# EDP_Retrofit.net
KiCad netlist of a schematic drawn in Altium Designer
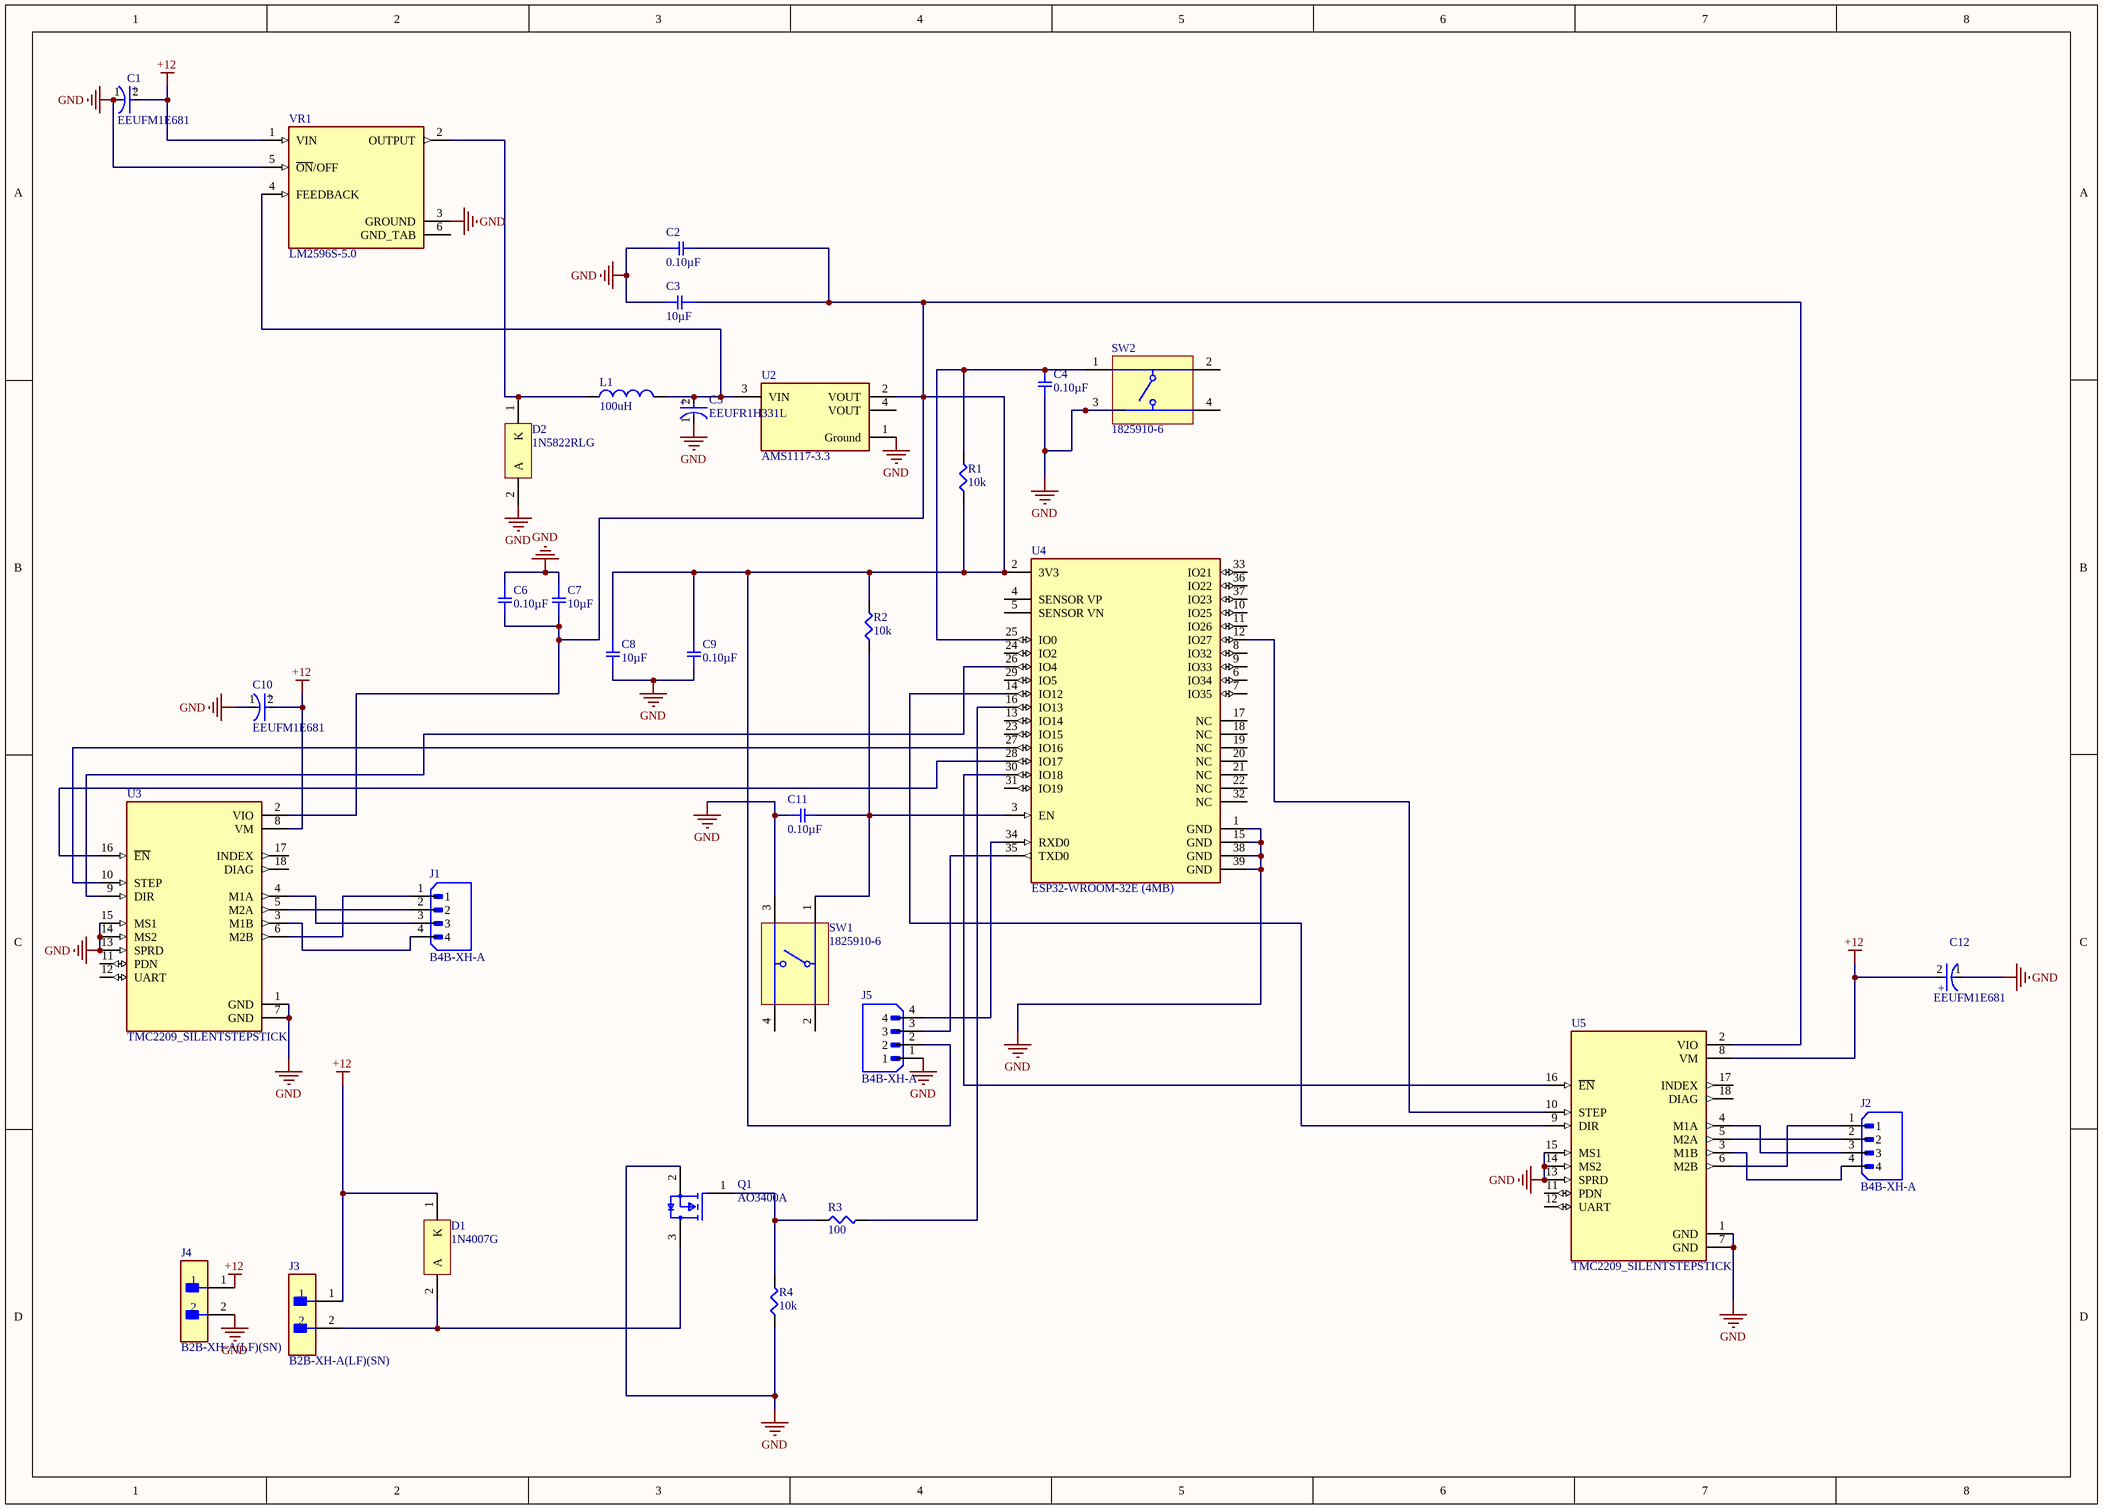
[diagram p0: EDP_Retrofit.SchDoc]

(export (version "E")
  (design (tool "Eeschema 10.0.6"))
  (components
    (comp (ref "C1")
      (value "EEUFM1E681")
      (footprint "FP-RAD-TH-D_10_0_5-L_20_2-MFG")
      (description "Aluminum Electrolytic Capacitors (Radial Lead Type) 680uF ±20% 25V")
      (fields (field (name "VOLTAGE") "25V") (field (name "TOLERANCE") "20%"))
      (libsource (lib "Altium Content Vault") (part "203bc49f2ac43e59fd269a8c329ed05"))
    )
    (comp (ref "C2")
      (value "0.10µF")
      (footprint "SMD-0805C")
      (description "CAP CER 0.1UF 25V X7R 0805")
      (fields
        (field (name "DIGI-KEY PART NUMBER") "490-1673-1-ND")
        (field (name "PART NUMBER") "GRM21BR71E104KA01L")
      )
      (libsource (lib "capacitor_murata_0805") (part "GRM21BR71E104KA01L"))
    )
    (comp (ref "C3")
      (value "10µF")
      (footprint "SMD-0805C")
      (description "CAP CER 10UF 10V X7R 0805")
      (fields
        (field (name "DIGI-KEY PART NUMBER") "490-12646-1-ND")
        (field (name "PART NUMBER") "GCJ21BR71A106KE01L")
      )
      (libsource (lib "capacitor_murata_0805") (part "GCJ21BR71A106KE01L"))
    )
    (comp (ref "C4")
      (value "0.10µF")
      (footprint "SMD-0805C")
      (description "CAP CER 0.1UF 25V X7R 0805")
      (fields
        (field (name "DIGI-KEY PART NUMBER") "490-1673-1-ND")
        (field (name "PART NUMBER") "GRM21BR71E104KA01L")
      )
      (libsource (lib "capacitor_murata_0805") (part "GRM21BR71E104KA01L"))
    )
    (comp (ref "C5")
      (value "EEUFR1H331L")
      (footprint "FP-RAD-TH-D_10_0_5-L_25_2-MFG")
      (description "Aluminum Electrolytic Capacitors (Radial Lead Type) 330uF ±20% 50V")
      (libsource (lib "Altium Content Vault") (part "a00bbbee19879c290e62620ae7e47b1"))
    )
    (comp (ref "C6")
      (value "0.10µF")
      (footprint "SMD-0805C")
      (description "CAP CER 0.1UF 25V X7R 0805")
      (fields
        (field (name "DIGI-KEY PART NUMBER") "490-1673-1-ND")
        (field (name "PART NUMBER") "GRM21BR71E104KA01L")
      )
      (libsource (lib "capacitor_murata_0805") (part "GRM21BR71E104KA01L"))
    )
    (comp (ref "C7")
      (value "10µF")
      (footprint "SMD-0805C")
      (description "CAP CER 10UF 10V X7R 0805")
      (fields
        (field (name "DIGI-KEY PART NUMBER") "490-12646-1-ND")
        (field (name "PART NUMBER") "GCJ21BR71A106KE01L")
      )
      (libsource (lib "capacitor_murata_0805") (part "GCJ21BR71A106KE01L"))
    )
    (comp (ref "C8")
      (value "10µF")
      (footprint "SMD-0805C")
      (description "CAP CER 10UF 10V X7R 0805")
      (fields
        (field (name "DIGI-KEY PART NUMBER") "490-12646-1-ND")
        (field (name "PART NUMBER") "GCJ21BR71A106KE01L")
      )
      (libsource (lib "capacitor_murata_0805") (part "GCJ21BR71A106KE01L"))
    )
    (comp (ref "C9")
      (value "0.10µF")
      (footprint "SMD-0805C")
      (description "CAP CER 0.1UF 25V X7R 0805")
      (fields
        (field (name "DIGI-KEY PART NUMBER") "490-1673-1-ND")
        (field (name "PART NUMBER") "GRM21BR71E104KA01L")
      )
      (libsource (lib "capacitor_murata_0805") (part "GRM21BR71E104KA01L"))
    )
    (comp (ref "C10")
      (value "EEUFM1E681")
      (footprint "FP-RAD-TH-D_10_0_5-L_20_2-MFG")
      (description "Aluminum Electrolytic Capacitors (Radial Lead Type) 680uF ±20% 25V")
      (fields (field (name "VOLTAGE") "25V") (field (name "TOLERANCE") "20%"))
      (libsource (lib "Altium Content Vault") (part "203bc49f2ac43e59fd269a8c329ed05"))
    )
    (comp (ref "C11")
      (value "0.10µF")
      (footprint "SMD-0805C")
      (description "CAP CER 0.1UF 25V X7R 0805")
      (fields
        (field (name "DIGI-KEY PART NUMBER") "490-1673-1-ND")
        (field (name "PART NUMBER") "GRM21BR71E104KA01L")
      )
      (libsource (lib "capacitor_murata_0805") (part "GRM21BR71E104KA01L"))
    )
    (comp (ref "C12")
      (value "EEUFM1E681")
      (footprint "FP-RAD-TH-D_10_0_5-L_20_2-MFG")
      (description "Aluminum Electrolytic Capacitors (Radial Lead Type) 680uF ±20% 25V")
      (fields (field (name "VOLTAGE") "25V") (field (name "TOLERANCE") "20%"))
      (libsource (lib "Altium Content Vault") (part "203bc49f2ac43e59fd269a8c329ed05"))
    )
    (comp (ref "D1")
      (value "1N4007G")
      (footprint "ONSC-AXIAL_LEAD-2-59-10_P")
      (description "Standard Recovery Rectifier, 2-Pin Axial_Lead, Pb-Free, Bulk Bag")
      (fields (field (name "MANUFACTURER") "On Semiconductor"))
      (libsource (lib "Altium Content Vault") (part "ONSC-D-K1A2-2_A"))
    )
    (comp (ref "D2")
      (value "1N5822RLG")
      (footprint "ONSC-AXIAL_LEAD-2-267-05_V")
      (description "Rectifier, 2-Pin Axial_Lead, Pb-Free, Tape and Reel")
      (fields (field (name "MANUFACTURER") "On Semiconductor"))
      (libsource (lib "Altium Content Vault") (part "ONSC-D-K1A2-2_A"))
    )
    (comp (ref "J1")
      (value "B4B-XH-A")
      (footprint "JST_B4B-XH-A")
      (description "Connector Header Through Hole 4 position 0.098 (2.50mm)")
      (fields (field (name "MF") "JST Sales"))
      (libsource (lib "B4B-XH-A") (part "B4B-XH-A"))
    )
    (comp (ref "J2")
      (value "B4B-XH-A")
      (footprint "JST_B4B-XH-A")
      (description "Connector Header Through Hole 4 position 0.098 (2.50mm)")
      (fields (field (name "MF") "JST Sales"))
      (libsource (lib "B4B-XH-A") (part "B4B-XH-A"))
    )
    (comp (ref "J3")
      (value "B2B-XH-A(LF)(SN)")
      (footprint "FP-B2B-XH-A_LF_SN-MFG")
      (description "CONN HEADER VERT 2POS 2.5MM")
      (libsource (lib "Altium Content Vault") (part "3bc925449376181038e59eaffc5286c"))
    )
    (comp (ref "J4")
      (value "B2B-XH-A(LF)(SN)")
      (footprint "FP-B2B-XH-A_LF_SN-MFG")
      (description "CONN HEADER VERT 2POS 2.5MM")
      (libsource (lib "Altium Content Vault") (part "3bc925449376181038e59eaffc5286c"))
    )
    (comp (ref "J5")
      (value "B4B-XH-A")
      (footprint "JST_B4B-XH-A")
      (description "Connector Header Through Hole 4 position 0.098 (2.50mm)")
      (fields (field (name "MF") "JST Sales"))
      (libsource (lib "") (part "B4B-XH-A_1"))
    )
    (comp (ref "L1")
      (value "100uH")
      (footprint "MY_0805")
      (description "Inductor")
      (fields (field (name "ASID PART NUMBER") "Inductor-AS"))
      (libsource (lib "Custom_Components") (part "Inductor"))
    )
    (comp (ref "Q1")
      (value "AO3400A")
      (footprint "FP-SOT23-MFG")
      (description "MOSFET N-CH 30V 5.7A SOT23")
      (libsource (lib "Altium Content Vault") (part "0a9ea7c96deaaede766a5b531c28de0"))
    )
    (comp (ref "R1")
      (value "10k")
      (footprint "SMD-0805-RES")
      (description "RES SMD 10K OHM 1% 1/8W 0805")
      (fields
        (field (name "PART NUMBER") "ERJ-6ENF1002V")
        (field (name "DIGI-KEY PART NUMBER") "P10.0KCCT-ND")
      )
      (libsource (lib "Panasonic_ERJ_0805") (part "ERJ-6ENF1002V"))
    )
    (comp (ref "R2")
      (value "10k")
      (footprint "SMD-0805-RES")
      (description "RES SMD 10K OHM 1% 1/8W 0805")
      (fields
        (field (name "PART NUMBER") "ERJ-6ENF1002V")
        (field (name "DIGI-KEY PART NUMBER") "P10.0KCCT-ND")
      )
      (libsource (lib "Panasonic_ERJ_0805") (part "ERJ-6ENF1002V"))
    )
    (comp (ref "R3")
      (value "100")
      (footprint "SMD-0805-RES")
      (description "RES SMD 100 OHM 1% 1/8W 0805")
      (fields (field (name "PART NUMBER") "ERJ-6ENF1000V") (field (name "DIGI-KEY PART NUMBER") "P100CCT-ND"))
      (libsource (lib "Panasonic_ERJ_0805") (part "ERJ-6ENF1000V"))
    )
    (comp (ref "R4")
      (value "10k")
      (footprint "SMD-0805-RES")
      (description "RES SMD 10K OHM 1% 1/8W 0805")
      (fields
        (field (name "PART NUMBER") "ERJ-6ENF1002V")
        (field (name "DIGI-KEY PART NUMBER") "P10.0KCCT-ND")
      )
      (libsource (lib "Panasonic_ERJ_0805") (part "ERJ-6ENF1002V"))
    )
    (comp (ref "SW1")
      (value "1825910-6")
      (footprint "TECO-1825910-6_V")
      (description "Tact Switch, SPST-NO, 0.05 A, -35 to 85 degC, 4-Pin THD, RoHS, Bulk")
      (fields (field (name "MANUFACTURER") "TE Connectivity"))
      (libsource (lib "") (part "SW-SPST-4_A_1"))
    )
    (comp (ref "SW2")
      (value "1825910-6")
      (footprint "TECO-1825910-6_V")
      (description "Tact Switch, SPST-NO, 0.05 A, -35 to 85 degC, 4-Pin THD, RoHS, Bulk")
      (fields (field (name "MANUFACTURER") "TE Connectivity"))
      (libsource (lib "Altium Content Vault") (part "SW-SPST-4_A"))
    )
    (comp (ref "U2")
      (value "AMS1117-3.3")
      (footprint "FP-AMS1117-IPC_C")
      (description "LDO Voltage Regulators 1A, 3.3V")
      (fields
        (field (name "OCTOPART") "https://octopart.com/ams1117-3.3-advanced+monolithic+systems-25899300")
        (field (name "MANUFACTURER") "Advanced Monolithic Systems")
      )
      (libsource (lib "Altium Content Vault") (part "8bdbb5f8e77002000e30dd2845d0354"))
    )
    (comp (ref "U3")
      (value "TMC2209_SILENTSTEPSTICK")
      (footprint "MODULE_TMC2209_SILENTSTEPSTICK")
      (description "TMC2209 Motor Controller/Driver Power Management Evaluation Board")
      (fields
        (field (name "MF") "Trinamic Motion Control GmbH")
        (field (name "MP") "TMC2209 SILENTSTEPSTICK")
      )
      (libsource (lib "TMC2209_SILENTSTEPSTICK") (part "TMC2209_SILENTSTEPSTICK"))
    )
    (comp (ref "U4")
      (value "ESP32-WROOM-32E (4MB)")
      (footprint "FP-ESP32-WROOM-32E_4MB-MFG")
      (description "RX TXRX MOD WIFI TRACE ANT SMD")
      (libsource (lib "Altium Content Vault") (part "7f842c3463a9561e2f6f9fdcd687e0f"))
    )
    (comp (ref "U5")
      (value "TMC2209_SILENTSTEPSTICK")
      (footprint "MODULE_TMC2209_SILENTSTEPSTICK")
      (description "TMC2209 Motor Controller/Driver Power Management Evaluation Board")
      (fields
        (field (name "MF") "Trinamic Motion Control GmbH")
        (field (name "MP") "TMC2209 SILENTSTEPSTICK")
      )
      (libsource (lib "TMC2209_SILENTSTEPSTICK") (part "TMC2209_SILENTSTEPSTICK"))
    )
    (comp (ref "VR1")
      (value "LM2596S-5.0")
      (footprint "TO170P1524X483-6N")
      (description "SIMPLE SWITCHERÂ® 4.5V to 40V, 3A Low Component Count Step-Down Regulator")
      (fields (field (name "MF") "Texas Instruments") (field (name "MP") "LM2596S-5.0/NOPB"))
      (libsource (lib "LM2596S-5.0") (part "LM2596S-5.0"))
    )
  )
  (nets
    (net (code "1") (name "+12") (class "Default")
      (node (ref "C1") (pin "2") (pinfunction "A_2") (pintype "passive"))
      (node (ref "C10") (pin "2") (pinfunction "A_2") (pintype "passive"))
      (node (ref "C12") (pin "2") (pinfunction "A_2") (pintype "passive"))
      (node (ref "D1") (pin "1") (pinfunction "K_1") (pintype "passive"))
      (node (ref "J3") (pin "1") (pinfunction "1_1") (pintype "passive"))
      (node (ref "J4") (pin "1") (pinfunction "1_1") (pintype "passive"))
      (node (ref "U3") (pin "8") (pinfunction "VM_8") (pintype "power_in"))
      (node (ref "U5") (pin "8") (pinfunction "VM_8") (pintype "power_in"))
      (node (ref "VR1") (pin "1") (pinfunction "VIN_1") (pintype "input"))
    )
    (net (code "2") (name "GND") (class "Default")
      (node (ref "C1") (pin "1") (pinfunction "C_1") (pintype "passive"))
      (node (ref "C10") (pin "1") (pinfunction "C_1") (pintype "passive"))
      (node (ref "C11") (pin "1") (pinfunction "1_1") (pintype "passive"))
      (node (ref "C12") (pin "1") (pinfunction "C_1") (pintype "passive"))
      (node (ref "C2") (pin "1") (pinfunction "1_1") (pintype "passive"))
      (node (ref "C3") (pin "2") (pinfunction "2_2") (pintype "passive"))
      (node (ref "C4") (pin "2") (pinfunction "2_2") (pintype "passive"))
      (node (ref "C5") (pin "1") (pinfunction "C_1") (pintype "passive"))
      (node (ref "C6") (pin "1") (pinfunction "1_1") (pintype "passive"))
      (node (ref "C7") (pin "1") (pinfunction "1_1") (pintype "passive"))
      (node (ref "C8") (pin "2") (pinfunction "2_2") (pintype "passive"))
      (node (ref "C9") (pin "2") (pinfunction "2_2") (pintype "passive"))
      (node (ref "D2") (pin "2") (pinfunction "A_2") (pintype "passive"))
      (node (ref "J4") (pin "2") (pinfunction "2_2") (pintype "passive"))
      (node (ref "J5") (pin "1") (pinfunction "1_1") (pintype "passive"))
      (node (ref "Q1") (pin "2") (pinfunction "S_2") (pintype "passive"))
      (node (ref "R4") (pin "1") (pinfunction "1_1") (pintype "passive"))
      (node (ref "SW1") (pin "3") (pinfunction "3_3") (pintype "passive"))
      (node (ref "SW2") (pin "3") (pinfunction "3_3") (pintype "passive"))
      (node (ref "U2") (pin "1") (pinfunction "Ground_1") (pintype "power_in"))
      (node (ref "U3") (pin "1") (pinfunction "GND_1") (pintype "power_in"))
      (node (ref "U3") (pin "13") (pinfunction "SPRD_13") (pintype "input"))
      (node (ref "U3") (pin "14") (pinfunction "MS2_14") (pintype "input"))
      (node (ref "U3") (pin "15") (pinfunction "MS1_15") (pintype "input"))
      (node (ref "U3") (pin "7") (pinfunction "GND_7") (pintype "power_in"))
      (node (ref "U4") (pin "1") (pinfunction "GND_1") (pintype "power_in"))
      (node (ref "U4") (pin "15") (pinfunction "GND_15") (pintype "power_in"))
      (node (ref "U4") (pin "38") (pinfunction "GND_38") (pintype "power_in"))
      (node (ref "U4") (pin "39") (pinfunction "GND_39") (pintype "power_in"))
      (node (ref "U5") (pin "1") (pinfunction "GND_1") (pintype "power_in"))
      (node (ref "U5") (pin "13") (pinfunction "SPRD_13") (pintype "input"))
      (node (ref "U5") (pin "14") (pinfunction "MS2_14") (pintype "input"))
      (node (ref "U5") (pin "15") (pinfunction "MS1_15") (pintype "input"))
      (node (ref "U5") (pin "7") (pinfunction "GND_7") (pintype "power_in"))
      (node (ref "VR1") (pin "3") (pinfunction "GROUND_3") (pintype "power_in"))
      (node (ref "VR1") (pin "5") (pinfunction "~{ON}/OFF_5") (pintype "input"))
    )
    (net (code "3") (name "Net-(C5-A)") (class "Default")
      (node (ref "C5") (pin "2") (pinfunction "A_2") (pintype "passive"))
      (node (ref "L1") (pin "2") (pinfunction "2_2") (pintype "passive"))
      (node (ref "U2") (pin "3") (pinfunction "VIN_3") (pintype "power_in"))
      (node (ref "VR1") (pin "4") (pinfunction "FEEDBACK_4") (pintype "input"))
    )
    (net (code "4") (name "Net-(D1-A)") (class "Default")
      (node (ref "D1") (pin "2") (pinfunction "A_2") (pintype "passive"))
      (node (ref "J3") (pin "2") (pinfunction "2_2") (pintype "passive"))
      (node (ref "Q1") (pin "3") (pinfunction "D_3") (pintype "passive"))
    )
    (net (code "5") (name "Net-(D2-K)") (class "Default")
      (node (ref "D2") (pin "1") (pinfunction "K_1") (pintype "passive"))
      (node (ref "L1") (pin "1") (pinfunction "1_1") (pintype "passive"))
      (node (ref "VR1") (pin "2") (pinfunction "OUTPUT_2") (pintype "output"))
    )
    (net (code "6") (name "Net-(Q1-G)") (class "Default")
      (node (ref "Q1") (pin "1") (pinfunction "G_1") (pintype "passive"))
      (node (ref "R3") (pin "1") (pinfunction "1_1") (pintype "passive"))
      (node (ref "R4") (pin "2") (pinfunction "2_2") (pintype "passive"))
    )
    (net (code "7") (name "Net-(U3-DIR)") (class "Default")
      (node (ref "U3") (pin "9") (pinfunction "DIR_9") (pintype "input"))
      (node (ref "U4") (pin "26") (pinfunction "IO4_26") (pintype "bidirectional"))
    )
    (net (code "8") (name "Net-(U3-M1A)") (class "Default")
      (node (ref "J1") (pin "3") (pinfunction "3_3") (pintype "passive"))
      (node (ref "U3") (pin "4") (pinfunction "M1A_4") (pintype "output"))
    )
    (net (code "9") (name "Net-(U3-M1B)") (class "Default")
      (node (ref "J1") (pin "4") (pinfunction "4_4") (pintype "passive"))
      (node (ref "U3") (pin "3") (pinfunction "M1B_3") (pintype "output"))
    )
    (net (code "10") (name "Net-(U3-M2A)") (class "Default")
      (node (ref "J1") (pin "2") (pinfunction "2_2") (pintype "passive"))
      (node (ref "U3") (pin "5") (pinfunction "M2A_5") (pintype "output"))
    )
    (net (code "11") (name "Net-(U3-M2B)") (class "Default")
      (node (ref "J1") (pin "1") (pinfunction "1_1") (pintype "passive"))
      (node (ref "U3") (pin "6") (pinfunction "M2B_6") (pintype "output"))
    )
    (net (code "12") (name "Net-(U3-STEP)") (class "Default")
      (node (ref "U3") (pin "10") (pinfunction "STEP_10") (pintype "input"))
      (node (ref "U4") (pin "27") (pinfunction "IO16_27") (pintype "bidirectional"))
    )
    (net (code "13") (name "Net-(U3-VIO)") (class "Default")
      (node (ref "C2") (pin "2") (pinfunction "2_2") (pintype "passive"))
      (node (ref "C3") (pin "1") (pinfunction "1_1") (pintype "passive"))
      (node (ref "C6") (pin "2") (pinfunction "2_2") (pintype "passive"))
      (node (ref "C7") (pin "2") (pinfunction "2_2") (pintype "passive"))
      (node (ref "C8") (pin "1") (pinfunction "1_1") (pintype "passive"))
      (node (ref "C9") (pin "1") (pinfunction "1_1") (pintype "passive"))
      (node (ref "J5") (pin "2") (pinfunction "2_2") (pintype "passive"))
      (node (ref "R1") (pin "1") (pinfunction "1_1") (pintype "passive"))
      (node (ref "R2") (pin "2") (pinfunction "2_2") (pintype "passive"))
      (node (ref "U2") (pin "2") (pinfunction "VOUT_2") (pintype "passive"))
      (node (ref "U3") (pin "2") (pinfunction "VIO_2") (pintype "power_in"))
      (node (ref "U4") (pin "2") (pinfunction "3V3_2") (pintype "power_in"))
      (node (ref "U5") (pin "2") (pinfunction "VIO_2") (pintype "power_in"))
    )
    (net (code "14") (name "Net-(U3-~{EN})") (class "Default")
      (node (ref "U3") (pin "16") (pinfunction "~{EN}_16") (pintype "input"))
      (node (ref "U4") (pin "28") (pinfunction "IO17_28") (pintype "bidirectional"))
    )
    (net (code "15") (name "Net-(U4-EN)") (class "Default")
      (node (ref "C11") (pin "2") (pinfunction "2_2") (pintype "passive"))
      (node (ref "R2") (pin "1") (pinfunction "1_1") (pintype "passive"))
      (node (ref "SW1") (pin "1") (pinfunction "1_1") (pintype "passive"))
      (node (ref "U4") (pin "3") (pinfunction "EN_3") (pintype "input"))
    )
    (net (code "16") (name "Net-(U4-IO0)") (class "Default")
      (node (ref "C4") (pin "1") (pinfunction "1_1") (pintype "passive"))
      (node (ref "R1") (pin "2") (pinfunction "2_2") (pintype "passive"))
      (node (ref "SW2") (pin "1") (pinfunction "1_1") (pintype "passive"))
      (node (ref "U4") (pin "25") (pinfunction "IO0_25") (pintype "bidirectional"))
    )
    (net (code "17") (name "Net-(U4-IO12)") (class "Default")
      (node (ref "U4") (pin "14") (pinfunction "IO12_14") (pintype "bidirectional"))
      (node (ref "U5") (pin "9") (pinfunction "DIR_9") (pintype "input"))
    )
    (net (code "18") (name "Net-(U4-IO13)") (class "Default")
      (node (ref "R3") (pin "2") (pinfunction "2_2") (pintype "passive"))
      (node (ref "U4") (pin "16") (pinfunction "IO13_16") (pintype "bidirectional"))
    )
    (net (code "19") (name "Net-(U4-IO18)") (class "Default")
      (node (ref "U4") (pin "30") (pinfunction "IO18_30") (pintype "bidirectional"))
      (node (ref "U5") (pin "16") (pinfunction "~{EN}_16") (pintype "input"))
    )
    (net (code "20") (name "Net-(U4-IO27)") (class "Default")
      (node (ref "U4") (pin "12") (pinfunction "IO27_12") (pintype "bidirectional"))
      (node (ref "U5") (pin "10") (pinfunction "STEP_10") (pintype "input"))
    )
    (net (code "21") (name "Net-(U4-RXD0)") (class "Default")
      (node (ref "J5") (pin "4") (pinfunction "4_4") (pintype "passive"))
      (node (ref "U4") (pin "34") (pinfunction "RXD0_34") (pintype "input"))
    )
    (net (code "22") (name "Net-(U4-TXD0)") (class "Default")
      (node (ref "J5") (pin "3") (pinfunction "3_3") (pintype "passive"))
      (node (ref "U4") (pin "35") (pinfunction "TXD0_35") (pintype "output"))
    )
    (net (code "23") (name "Net-(U5-M1A)") (class "Default")
      (node (ref "J2") (pin "3") (pinfunction "3_3") (pintype "passive"))
      (node (ref "U5") (pin "4") (pinfunction "M1A_4") (pintype "output"))
    )
    (net (code "24") (name "Net-(U5-M1B)") (class "Default")
      (node (ref "J2") (pin "4") (pinfunction "4_4") (pintype "passive"))
      (node (ref "U5") (pin "3") (pinfunction "M1B_3") (pintype "output"))
    )
    (net (code "25") (name "Net-(U5-M2A)") (class "Default")
      (node (ref "J2") (pin "2") (pinfunction "2_2") (pintype "passive"))
      (node (ref "U5") (pin "5") (pinfunction "M2A_5") (pintype "output"))
    )
    (net (code "26") (name "Net-(U5-M2B)") (class "Default")
      (node (ref "J2") (pin "1") (pinfunction "1_1") (pintype "passive"))
      (node (ref "U5") (pin "6") (pinfunction "M2B_6") (pintype "output"))
    )
    (net (code "27") (name "unconnected-(SW1-Pad2)") (class "Default")
      (node (ref "SW1") (pin "2") (pinfunction "2_2") (pintype "passive"))
    )
    (net (code "28") (name "unconnected-(SW1-Pad4)") (class "Default")
      (node (ref "SW1") (pin "4") (pinfunction "4_4") (pintype "passive"))
    )
    (net (code "29") (name "unconnected-(SW2-Pad2)") (class "Default")
      (node (ref "SW2") (pin "2") (pinfunction "2_2") (pintype "passive"))
    )
    (net (code "30") (name "unconnected-(SW2-Pad4)") (class "Default")
      (node (ref "SW2") (pin "4") (pinfunction "4_4") (pintype "passive"))
    )
    (net (code "31") (name "unconnected-(U2-VOUT-Pad4)") (class "Default")
      (node (ref "U2") (pin "4") (pinfunction "VOUT_4") (pintype "passive"))
    )
    (net (code "32") (name "unconnected-(U3-DIAG-Pad18)") (class "Default")
      (node (ref "U3") (pin "18") (pinfunction "DIAG_18") (pintype "output"))
    )
    (net (code "33") (name "unconnected-(U3-INDEX-Pad17)") (class "Default")
      (node (ref "U3") (pin "17") (pinfunction "INDEX_17") (pintype "output"))
    )
    (net (code "34") (name "unconnected-(U3-PDN-Pad11)") (class "Default")
      (node (ref "U3") (pin "11") (pinfunction "PDN_11") (pintype "bidirectional"))
    )
    (net (code "35") (name "unconnected-(U3-UART-Pad12)") (class "Default")
      (node (ref "U3") (pin "12") (pinfunction "UART_12") (pintype "bidirectional"))
    )
    (net (code "36") (name "unconnected-(U4-IO2-Pad24)") (class "Default")
      (node (ref "U4") (pin "24") (pinfunction "IO2_24") (pintype "bidirectional"))
    )
    (net (code "37") (name "unconnected-(U4-IO5-Pad29)") (class "Default")
      (node (ref "U4") (pin "29") (pinfunction "IO5_29") (pintype "bidirectional"))
    )
    (net (code "38") (name "unconnected-(U4-IO14-Pad13)") (class "Default")
      (node (ref "U4") (pin "13") (pinfunction "IO14_13") (pintype "bidirectional"))
    )
    (net (code "39") (name "unconnected-(U4-IO15-Pad23)") (class "Default")
      (node (ref "U4") (pin "23") (pinfunction "IO15_23") (pintype "bidirectional"))
    )
    (net (code "40") (name "unconnected-(U4-IO19-Pad31)") (class "Default")
      (node (ref "U4") (pin "31") (pinfunction "IO19_31") (pintype "bidirectional"))
    )
    (net (code "41") (name "unconnected-(U4-IO21-Pad33)") (class "Default")
      (node (ref "U4") (pin "33") (pinfunction "IO21_33") (pintype "bidirectional"))
    )
    (net (code "42") (name "unconnected-(U4-IO22-Pad36)") (class "Default")
      (node (ref "U4") (pin "36") (pinfunction "IO22_36") (pintype "bidirectional"))
    )
    (net (code "43") (name "unconnected-(U4-IO23-Pad37)") (class "Default")
      (node (ref "U4") (pin "37") (pinfunction "IO23_37") (pintype "bidirectional"))
    )
    (net (code "44") (name "unconnected-(U4-IO25-Pad10)") (class "Default")
      (node (ref "U4") (pin "10") (pinfunction "IO25_10") (pintype "bidirectional"))
    )
    (net (code "45") (name "unconnected-(U4-IO26-Pad11)") (class "Default")
      (node (ref "U4") (pin "11") (pinfunction "IO26_11") (pintype "bidirectional"))
    )
    (net (code "46") (name "unconnected-(U4-IO32-Pad8)") (class "Default")
      (node (ref "U4") (pin "8") (pinfunction "IO32_8") (pintype "bidirectional"))
    )
    (net (code "47") (name "unconnected-(U4-IO33-Pad9)") (class "Default")
      (node (ref "U4") (pin "9") (pinfunction "IO33_9") (pintype "bidirectional"))
    )
    (net (code "48") (name "unconnected-(U4-IO34-Pad6)") (class "Default")
      (node (ref "U4") (pin "6") (pinfunction "IO34_6") (pintype "bidirectional"))
    )
    (net (code "49") (name "unconnected-(U4-IO35-Pad7)") (class "Default")
      (node (ref "U4") (pin "7") (pinfunction "IO35_7") (pintype "bidirectional"))
    )
    (net (code "50") (name "unconnected-(U4-NC-Pad17)") (class "Default")
      (node (ref "U4") (pin "17") (pinfunction "NC_17") (pintype "passive"))
    )
    (net (code "51") (name "unconnected-(U4-NC-Pad18)") (class "Default")
      (node (ref "U4") (pin "18") (pinfunction "NC_18") (pintype "passive"))
    )
    (net (code "52") (name "unconnected-(U4-NC-Pad19)") (class "Default")
      (node (ref "U4") (pin "19") (pinfunction "NC_19") (pintype "passive"))
    )
    (net (code "53") (name "unconnected-(U4-NC-Pad20)") (class "Default")
      (node (ref "U4") (pin "20") (pinfunction "NC_20") (pintype "passive"))
    )
    (net (code "54") (name "unconnected-(U4-NC-Pad21)") (class "Default")
      (node (ref "U4") (pin "21") (pinfunction "NC_21") (pintype "passive"))
    )
    (net (code "55") (name "unconnected-(U4-NC-Pad22)") (class "Default")
      (node (ref "U4") (pin "22") (pinfunction "NC_22") (pintype "passive"))
    )
    (net (code "56") (name "unconnected-(U4-NC-Pad32)") (class "Default")
      (node (ref "U4") (pin "32") (pinfunction "NC_32") (pintype "passive"))
    )
    (net (code "57") (name "unconnected-(U4-SENSOR_VN-Pad5)") (class "Default")
      (node (ref "U4") (pin "5") (pinfunction "SENSOR_VN_5") (pintype "passive"))
    )
    (net (code "58") (name "unconnected-(U4-SENSOR_VP-Pad4)") (class "Default")
      (node (ref "U4") (pin "4") (pinfunction "SENSOR_VP_4") (pintype "passive"))
    )
    (net (code "59") (name "unconnected-(U5-DIAG-Pad18)") (class "Default")
      (node (ref "U5") (pin "18") (pinfunction "DIAG_18") (pintype "output"))
    )
    (net (code "60") (name "unconnected-(U5-INDEX-Pad17)") (class "Default")
      (node (ref "U5") (pin "17") (pinfunction "INDEX_17") (pintype "output"))
    )
    (net (code "61") (name "unconnected-(U5-PDN-Pad11)") (class "Default")
      (node (ref "U5") (pin "11") (pinfunction "PDN_11") (pintype "bidirectional"))
    )
    (net (code "62") (name "unconnected-(U5-UART-Pad12)") (class "Default")
      (node (ref "U5") (pin "12") (pinfunction "UART_12") (pintype "bidirectional"))
    )
    (net (code "63") (name "unconnected-(VR1-GND_TAB-Pad6)") (class "Default")
      (node (ref "VR1") (pin "6") (pinfunction "GND_TAB_6") (pintype "power_in"))
    )
  )
)
